# Sheet1.net
KiCad netlist of a schematic drawn in Altium Designer
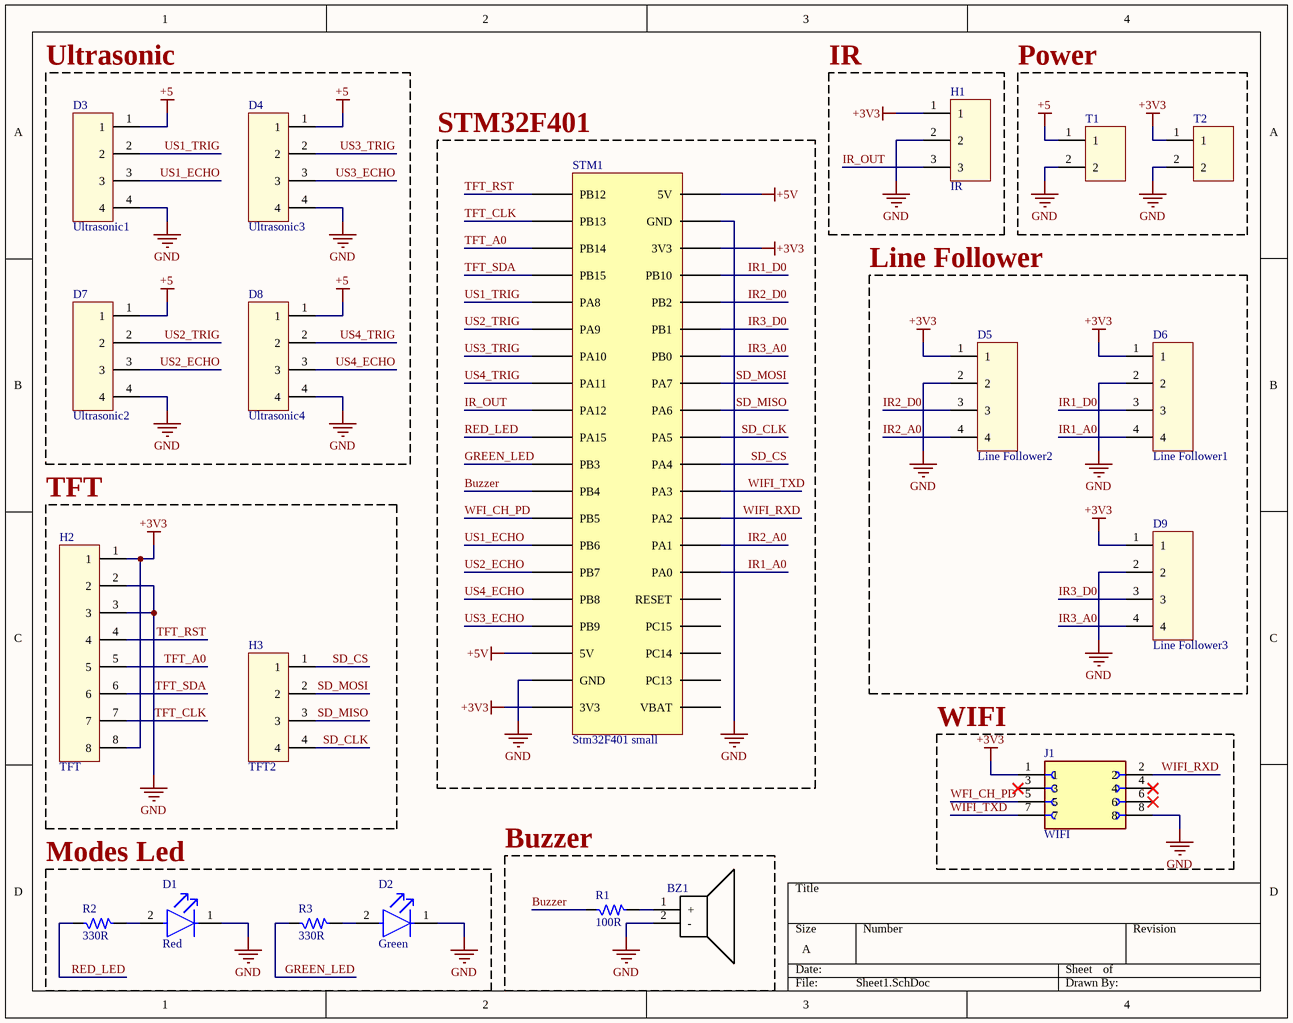
[diagram p0: Sheet1.SchDoc]

(export (version "E")
  (design (tool "Eeschema 10.0.6"))
  (components
    (comp (ref "BZ1")
      (value "PS1440P02BT")
      (footprint "BUZZ_PS1440P02BT_TH")
      (description "Buzzers Transducer, Externally Driven Piezo 3V  4kHz 75dB @ 3V, 10cm Through Hole PC Pins")
      (fields (field (name "MANUFACTURER") "TDK Corporation"))
      (libsource (lib "My Library") (part "BUZZ_PS1440P02BT-30V-TH"))
    )
    (comp (ref "D1")
      (value "Red")
      (footprint "FP-HLMP-1301-MFG")
      (description "LED RED DIFFUSED T-1 T/H")
      (fields
        (field (name "MANUFACTURER PART NUMBER") "HLMP-1301")
        (field (name "OCTOPART") "https://octopart.com/hlmp-1301-broadcom-71130345")
      )
      (libsource (lib "Altium Content Vault") (part "8706943c75ba83719d021d2fdc84c58"))
    )
    (comp (ref "D2")
      (value "Green")
      (footprint "FP-HLMP-1503-MFG")
      (description "LED GREEN DIFFUSED T-1 T/H")
      (fields (field (name "MANUFACTURER") "Broadcom") (field (name "MANUFACTURER PART NUMBER") "HLMP-1503"))
      (libsource (lib "Altium Content Vault") (part "8706943c75ba83719d021d2fdc84c58"))
    )
    (comp (ref "D3")
      (value "Ultrasonic1")
      (footprint "DATA_PIN_HEADER_4_2.54m")
      (libsource (lib "My Library") (part "DATA_PIN_HEADER_4_2.54m"))
    )
    (comp (ref "D4")
      (value "Ultrasonic3")
      (footprint "DATA_PIN_HEADER_4_2.54m")
      (libsource (lib "My Library") (part "DATA_PIN_HEADER_4_2.54m"))
    )
    (comp (ref "D5")
      (value "Line Follower2")
      (footprint "DATA_PIN_HEADER_4_2.54m")
      (libsource (lib "") (part "DATA_PIN_HEADER_4_2.54m_1"))
    )
    (comp (ref "D6")
      (value "Line Follower1")
      (footprint "DATA_PIN_HEADER_4_2.54m")
      (libsource (lib "") (part "DATA_PIN_HEADER_4_2.54m_1"))
    )
    (comp (ref "D7")
      (value "Ultrasonic2")
      (footprint "DATA_PIN_HEADER_4_2.54m")
      (libsource (lib "My Library") (part "DATA_PIN_HEADER_4_2.54m"))
    )
    (comp (ref "D8")
      (value "Ultrasonic4")
      (footprint "DATA_PIN_HEADER_4_2.54m")
      (libsource (lib "My Library") (part "DATA_PIN_HEADER_4_2.54m"))
    )
    (comp (ref "D9")
      (value "Line Follower3")
      (footprint "DATA_PIN_HEADER_4_2.54m")
      (libsource (lib "") (part "DATA_PIN_HEADER_4_2.54m_1"))
    )
    (comp (ref "H1")
      (value "IR")
      (footprint "Female_Header_3")
      (libsource (lib "My Library") (part "FEMALE_HEADER_3"))
    )
    (comp (ref "H2")
      (value "TFT")
      (footprint "Female_Header_8")
      (libsource (lib "My Library") (part "FEMALE_HEADER_8"))
    )
    (comp (ref "H3")
      (value "TFT2")
      (footprint "Female_Header_4")
      (libsource (lib "My Library") (part "FEMALE_HEADER_4"))
    )
    (comp (ref "J1")
      (value "WIFI")
      (footprint "SULLINS_PPPC042LFBN-RC")
      (description "8 Position Total Dual Row 2.54 mm Pitch Straight Female Header")
      (fields (field (name "MF") "Sullins Connector Solutions") (field (name "MP") "PPPC042LFBNRC"))
      (libsource (lib "My Library") (part "PPPC042LFBN-RC"))
    )
    (comp (ref "R1")
      (value "100R")
      (footprint "RES_1206")
      (description "10 Ohms ±5% 0.25W, 1/4W Chip Resistor 1206 (3216 Metric) Automotive AEC-Q200 Thick Film")
      (fields
        (field (name "MANUFACTURER") "Yageo")
        (field (name "MANUFACTURER PART NUMBER") "RMCF1206JT10R0")
      )
      (libsource (lib "My Library") (part "RES_10R-0.25W-5%-1206"))
    )
    (comp (ref "R2")
      (value "330R")
      (footprint "RES_0603")
      (description "2.2 kOhms ±1% 0.1W, 1/10W Chip Resistor 0603 (1608 Metric) Automotive AEC-Q200 Thick Film")
      (fields (field (name "MANUFACTURER") "Walsin") (field (name "MANUFACTURER PART NUMBER") "WR06X2201FTL"))
      (libsource (lib "My Library") (part "RES_2.2K-0.1W-1%-0603"))
    )
    (comp (ref "R3")
      (value "330R")
      (footprint "RES_0603")
      (description "2.2 kOhms ±1% 0.1W, 1/10W Chip Resistor 0603 (1608 Metric) Automotive AEC-Q200 Thick Film")
      (fields (field (name "MANUFACTURER") "Walsin") (field (name "MANUFACTURER PART NUMBER") "WR06X2201FTL"))
      (libsource (lib "My Library") (part "RES_2.2K-0.1W-1%-0603"))
    )
    (comp (ref "STM1")
      (value "Stm32F401 small")
      (footprint "Stm32F401CCU6")
      (libsource (lib "My Library") (part "Stm32F401 small"))
    )
    (comp (ref "T1")
      (value "Terminal_block_2pins_5mm")
      (footprint "Terminal_block_2pins_5mm")
      (libsource (lib "My Library") (part "Terminal_block_2pins_5mm"))
    )
    (comp (ref "T2")
      (value "Terminal_block_2pins_5mm")
      (footprint "Terminal_block_2pins_5mm")
      (libsource (lib "My Library") (part "Terminal_block_2pins_5mm"))
    )
  )
  (nets
    (net (code "1") (name "+3V3") (class "Default")
      (node (ref "D5") (pin "1") (pinfunction "1_1") (pintype "passive"))
      (node (ref "D6") (pin "1") (pinfunction "1_1") (pintype "passive"))
      (node (ref "D9") (pin "1") (pinfunction "1_1") (pintype "passive"))
      (node (ref "H1") (pin "1") (pinfunction "1_1") (pintype "passive"))
      (node (ref "H2") (pin "1") (pinfunction "1_1") (pintype "passive"))
      (node (ref "H2") (pin "8") (pinfunction "8_8") (pintype "passive"))
      (node (ref "J1") (pin "1") (pinfunction "1_1") (pintype "passive"))
      (node (ref "STM1") (pin "3V3") (pinfunction "3V3_3V3") (pintype "passive"))
      (node (ref "T2") (pin "1") (pinfunction "1_1") (pintype "passive"))
    )
    (net (code "2") (name "+5") (class "Default")
      (node (ref "D3") (pin "1") (pinfunction "1_1") (pintype "passive"))
      (node (ref "D4") (pin "1") (pinfunction "1_1") (pintype "passive"))
      (node (ref "D7") (pin "1") (pinfunction "1_1") (pintype "passive"))
      (node (ref "D8") (pin "1") (pinfunction "1_1") (pintype "passive"))
      (node (ref "T1") (pin "1") (pinfunction "1_1") (pintype "passive"))
    )
    (net (code "3") (name "+5V") (class "Default")
      (node (ref "STM1") (pin "5V") (pinfunction "5V_5V") (pintype "passive"))
    )
    (net (code "4") (name "/Buzzer") (class "Default")
      (node (ref "R1") (pin "1") (pinfunction "1_1") (pintype "passive"))
      (node (ref "STM1") (pin "PB4") (pinfunction "PB4_PB4") (pintype "passive"))
    )
    (net (code "5") (name "/GREEN_LED") (class "Default")
      (node (ref "R3") (pin "1") (pinfunction "1_1") (pintype "passive"))
      (node (ref "STM1") (pin "PB3") (pinfunction "PB3_PB3") (pintype "passive"))
    )
    (net (code "6") (name "/IR1_A0") (class "Default")
      (node (ref "D6") (pin "4") (pinfunction "4_4") (pintype "passive"))
      (node (ref "STM1") (pin "PA0") (pinfunction "PA0_PA0") (pintype "passive"))
    )
    (net (code "7") (name "/IR1_D0") (class "Default")
      (node (ref "D6") (pin "3") (pinfunction "3_3") (pintype "passive"))
      (node (ref "STM1") (pin "PB10") (pinfunction "PB10_PB10") (pintype "passive"))
    )
    (net (code "8") (name "/IR2_A0") (class "Default")
      (node (ref "D5") (pin "4") (pinfunction "4_4") (pintype "passive"))
      (node (ref "STM1") (pin "PA1") (pinfunction "PA1_PA1") (pintype "passive"))
    )
    (net (code "9") (name "/IR2_D0") (class "Default")
      (node (ref "D5") (pin "3") (pinfunction "3_3") (pintype "passive"))
      (node (ref "STM1") (pin "PB2") (pinfunction "PB2_PB2") (pintype "passive"))
    )
    (net (code "10") (name "/IR3_A0") (class "Default")
      (node (ref "D9") (pin "4") (pinfunction "4_4") (pintype "passive"))
      (node (ref "STM1") (pin "PB0") (pinfunction "PB0_PB0") (pintype "passive"))
    )
    (net (code "11") (name "/IR3_D0") (class "Default")
      (node (ref "D9") (pin "3") (pinfunction "3_3") (pintype "passive"))
      (node (ref "STM1") (pin "PB1") (pinfunction "PB1_PB1") (pintype "passive"))
    )
    (net (code "12") (name "/IR_OUT") (class "Default")
      (node (ref "H1") (pin "3") (pinfunction "3_3") (pintype "passive"))
      (node (ref "STM1") (pin "PA12") (pinfunction "PA12_PA12") (pintype "passive"))
    )
    (net (code "13") (name "/RED_LED") (class "Default")
      (node (ref "R2") (pin "1") (pinfunction "1_1") (pintype "passive"))
      (node (ref "STM1") (pin "PA15") (pinfunction "PA15_PA15") (pintype "passive"))
    )
    (net (code "14") (name "/SD_CLK") (class "Default")
      (node (ref "H3") (pin "4") (pinfunction "4_4") (pintype "passive"))
      (node (ref "STM1") (pin "PA5") (pinfunction "PA5_PA5") (pintype "passive"))
    )
    (net (code "15") (name "/SD_CS") (class "Default")
      (node (ref "H3") (pin "1") (pinfunction "1_1") (pintype "passive"))
      (node (ref "STM1") (pin "PA4") (pinfunction "PA4_PA4") (pintype "passive"))
    )
    (net (code "16") (name "/SD_MISO") (class "Default")
      (node (ref "H3") (pin "3") (pinfunction "3_3") (pintype "passive"))
      (node (ref "STM1") (pin "PA6") (pinfunction "PA6_PA6") (pintype "passive"))
    )
    (net (code "17") (name "/SD_MOSI") (class "Default")
      (node (ref "H3") (pin "2") (pinfunction "2_2") (pintype "passive"))
      (node (ref "STM1") (pin "PA7") (pinfunction "PA7_PA7") (pintype "passive"))
    )
    (net (code "18") (name "/TFT_A0") (class "Default")
      (node (ref "H2") (pin "5") (pinfunction "5_5") (pintype "passive"))
      (node (ref "STM1") (pin "PB14") (pinfunction "PB14_PB14") (pintype "passive"))
    )
    (net (code "19") (name "/TFT_CLK") (class "Default")
      (node (ref "H2") (pin "7") (pinfunction "7_7") (pintype "passive"))
      (node (ref "STM1") (pin "PB13") (pinfunction "PB13_PB13") (pintype "passive"))
    )
    (net (code "20") (name "/TFT_RST") (class "Default")
      (node (ref "H2") (pin "4") (pinfunction "4_4") (pintype "passive"))
      (node (ref "STM1") (pin "PB12") (pinfunction "PB12_PB12") (pintype "passive"))
    )
    (net (code "21") (name "/TFT_SDA") (class "Default")
      (node (ref "H2") (pin "6") (pinfunction "6_6") (pintype "passive"))
      (node (ref "STM1") (pin "PB15") (pinfunction "PB15_PB15") (pintype "passive"))
    )
    (net (code "22") (name "/US1_ECHO") (class "Default")
      (node (ref "D3") (pin "3") (pinfunction "3_3") (pintype "passive"))
      (node (ref "STM1") (pin "PB6") (pinfunction "PB6_PB6") (pintype "passive"))
    )
    (net (code "23") (name "/US1_TRIG") (class "Default")
      (node (ref "D3") (pin "2") (pinfunction "2_2") (pintype "passive"))
      (node (ref "STM1") (pin "PA8") (pinfunction "PA8_PA8") (pintype "passive"))
    )
    (net (code "24") (name "/US2_ECHO") (class "Default")
      (node (ref "D7") (pin "3") (pinfunction "3_3") (pintype "passive"))
      (node (ref "STM1") (pin "PB7") (pinfunction "PB7_PB7") (pintype "passive"))
    )
    (net (code "25") (name "/US2_TRIG") (class "Default")
      (node (ref "D7") (pin "2") (pinfunction "2_2") (pintype "passive"))
      (node (ref "STM1") (pin "PA9") (pinfunction "PA9_PA9") (pintype "passive"))
    )
    (net (code "26") (name "/US3_ECHO") (class "Default")
      (node (ref "D4") (pin "3") (pinfunction "3_3") (pintype "passive"))
      (node (ref "STM1") (pin "PB9") (pinfunction "PB9_PB9") (pintype "passive"))
    )
    (net (code "27") (name "/US3_TRIG") (class "Default")
      (node (ref "D4") (pin "2") (pinfunction "2_2") (pintype "passive"))
      (node (ref "STM1") (pin "PA10") (pinfunction "PA10_PA10") (pintype "passive"))
    )
    (net (code "28") (name "/US4_ECHO") (class "Default")
      (node (ref "D8") (pin "3") (pinfunction "3_3") (pintype "passive"))
      (node (ref "STM1") (pin "PB8") (pinfunction "PB8_PB8") (pintype "passive"))
    )
    (net (code "29") (name "/US4_TRIG") (class "Default")
      (node (ref "D8") (pin "2") (pinfunction "2_2") (pintype "passive"))
      (node (ref "STM1") (pin "PA11") (pinfunction "PA11_PA11") (pintype "passive"))
    )
    (net (code "30") (name "/WFI_CH_PD") (class "Default")
      (node (ref "J1") (pin "5") (pinfunction "5_5") (pintype "passive"))
      (node (ref "STM1") (pin "PB5") (pinfunction "PB5_PB5") (pintype "passive"))
    )
    (net (code "31") (name "/WIFI_RXD") (class "Default")
      (node (ref "J1") (pin "2") (pinfunction "2_2") (pintype "passive"))
      (node (ref "STM1") (pin "PA2") (pinfunction "PA2_PA2") (pintype "passive"))
    )
    (net (code "32") (name "/WIFI_TXD") (class "Default")
      (node (ref "J1") (pin "7") (pinfunction "7_7") (pintype "passive"))
      (node (ref "STM1") (pin "PA3") (pinfunction "PA3_PA3") (pintype "passive"))
    )
    (net (code "33") (name "GND") (class "Default")
      (node (ref "BZ1") (pin "2") (pinfunction "-_2") (pintype "passive"))
      (node (ref "D1") (pin "1") (pinfunction "C_1") (pintype "passive"))
      (node (ref "D2") (pin "1") (pinfunction "C_1") (pintype "passive"))
      (node (ref "D3") (pin "4") (pinfunction "4_4") (pintype "passive"))
      (node (ref "D4") (pin "4") (pinfunction "4_4") (pintype "passive"))
      (node (ref "D5") (pin "2") (pinfunction "2_2") (pintype "passive"))
      (node (ref "D6") (pin "2") (pinfunction "2_2") (pintype "passive"))
      (node (ref "D7") (pin "4") (pinfunction "4_4") (pintype "passive"))
      (node (ref "D8") (pin "4") (pinfunction "4_4") (pintype "passive"))
      (node (ref "D9") (pin "2") (pinfunction "2_2") (pintype "passive"))
      (node (ref "H1") (pin "2") (pinfunction "2_2") (pintype "passive"))
      (node (ref "H2") (pin "2") (pinfunction "2_2") (pintype "passive"))
      (node (ref "H2") (pin "3") (pinfunction "3_3") (pintype "passive"))
      (node (ref "J1") (pin "8") (pinfunction "8_8") (pintype "passive"))
      (node (ref "STM1") (pin "GND") (pinfunction "GND_GND") (pintype "passive"))
      (node (ref "T1") (pin "2") (pinfunction "2_2") (pintype "passive"))
      (node (ref "T2") (pin "2") (pinfunction "2_2") (pintype "passive"))
    )
    (net (code "34") (name "Net-(BZ1-+)") (class "Default")
      (node (ref "BZ1") (pin "1") (pinfunction "+_1") (pintype "passive"))
      (node (ref "R1") (pin "2") (pinfunction "2_2") (pintype "passive"))
    )
    (net (code "35") (name "Net-(D1-A)") (class "Default")
      (node (ref "D1") (pin "2") (pinfunction "A_2") (pintype "passive"))
      (node (ref "R2") (pin "2") (pinfunction "2_2") (pintype "passive"))
    )
    (net (code "36") (name "Net-(D2-A)") (class "Default")
      (node (ref "D2") (pin "2") (pinfunction "A_2") (pintype "passive"))
      (node (ref "R3") (pin "2") (pinfunction "2_2") (pintype "passive"))
    )
    (net (code "37") (name "unconnected-(J1-Pad3)") (class "Default")
      (node (ref "J1") (pin "3") (pinfunction "3_3") (pintype "passive+no_connect"))
    )
    (net (code "38") (name "unconnected-(J1-Pad4)") (class "Default")
      (node (ref "J1") (pin "4") (pinfunction "4_4") (pintype "passive+no_connect"))
    )
    (net (code "39") (name "unconnected-(J1-Pad6)") (class "Default")
      (node (ref "J1") (pin "6") (pinfunction "6_6") (pintype "passive+no_connect"))
    )
    (net (code "40") (name "unconnected-(STM1-PadPC13)") (class "Default")
      (node (ref "STM1") (pin "PC13") (pinfunction "PC13_PC13") (pintype "passive"))
    )
    (net (code "41") (name "unconnected-(STM1-PadPC14)") (class "Default")
      (node (ref "STM1") (pin "PC14") (pinfunction "PC14_PC14") (pintype "passive"))
    )
    (net (code "42") (name "unconnected-(STM1-PadPC15)") (class "Default")
      (node (ref "STM1") (pin "PC15") (pinfunction "PC15_PC15") (pintype "passive"))
    )
    (net (code "43") (name "unconnected-(STM1-PadRESET)") (class "Default")
      (node (ref "STM1") (pin "RESET") (pinfunction "RESET_RESET") (pintype "passive"))
    )
    (net (code "44") (name "unconnected-(STM1-PadVBAT)") (class "Default")
      (node (ref "STM1") (pin "VBAT") (pinfunction "VBAT_VBAT") (pintype "passive"))
    )
  )
)
